# main_board.net
KiCad netlist of a schematic drawn in EAGLE
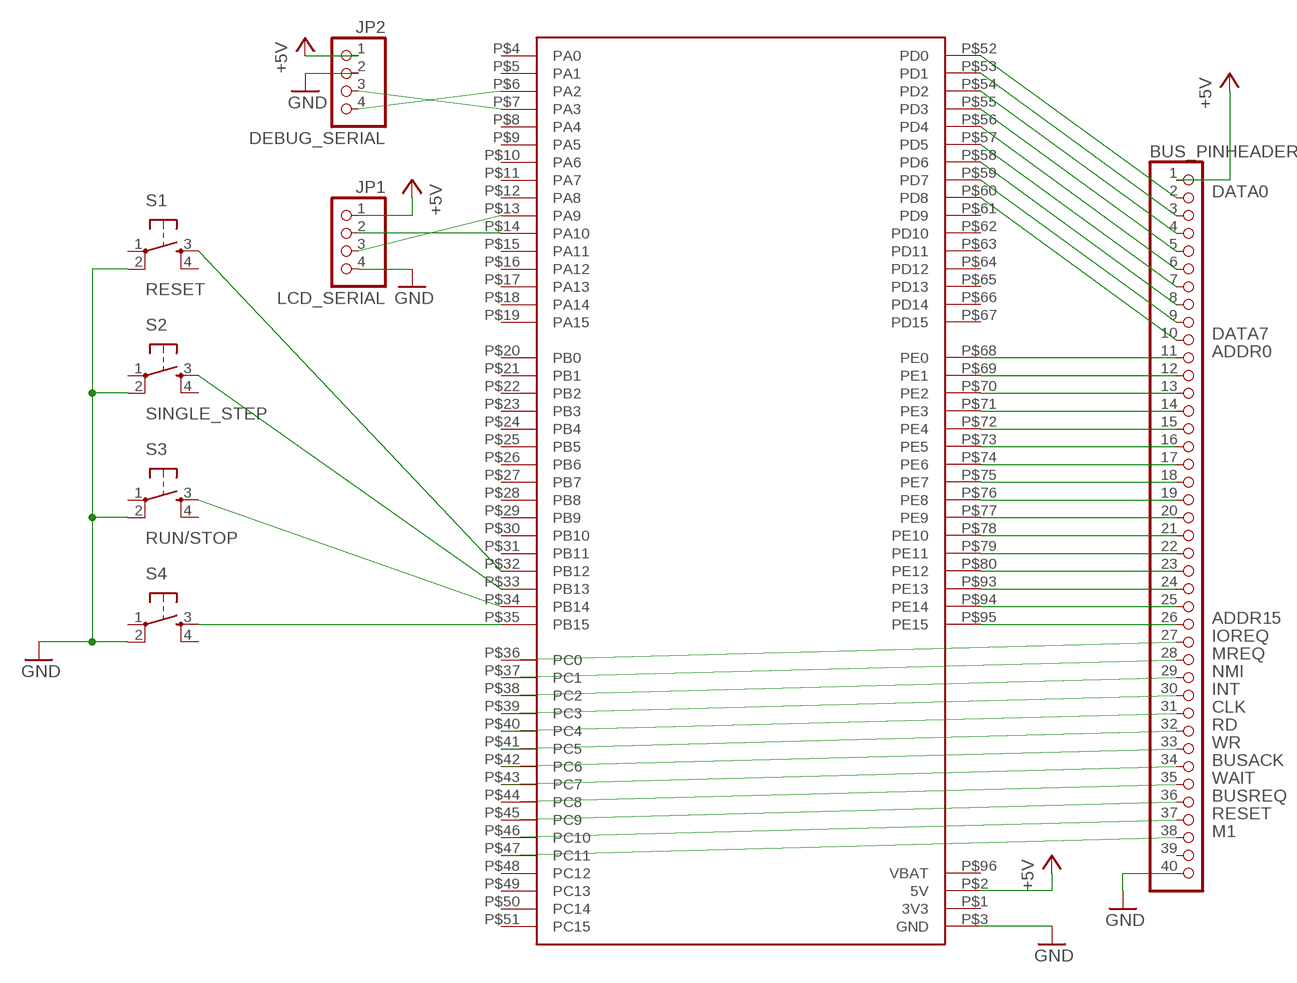
[diagram p0: schematic, sheet 1]

(export (version "E")
  (design (tool "Eeschema 10.0.6"))
  (components
    (comp (ref "BUS_PINHEADER")
      (value "PINHD-1X40")
      (footprint "eagle-import:1X40")
      (libsource (lib "eagle-import") (part "PINHD-1X40"))
    )
    (comp (ref "JP1")
      (value "LCD_SERIAL")
      (footprint "eagle-import:1X04")
      (libsource (lib "eagle-import") (part "PINHD-1X4"))
    )
    (comp (ref "JP2")
      (value "DEBUG_SERIAL")
      (footprint "eagle-import:1X04")
      (libsource (lib "eagle-import") (part "PINHD-1X4"))
    )
    (comp (ref "S1")
      (value "RESET")
      (footprint "eagle-import:TACTILE-PTH")
      (libsource (lib "eagle-import") (part "TAC_SWITCHPTH"))
    )
    (comp (ref "S2")
      (value "SINGLE_STEP")
      (footprint "eagle-import:TACTILE-PTH")
      (libsource (lib "eagle-import") (part "TAC_SWITCHPTH"))
    )
    (comp (ref "S3")
      (value "RUN/STOP")
      (footprint "eagle-import:TACTILE-PTH")
      (libsource (lib "eagle-import") (part "TAC_SWITCHPTH"))
    )
    (comp (ref "S4")
      (value "TAC_SWITCHPTH")
      (footprint "eagle-import:TACTILE-PTH")
      (libsource (lib "eagle-import") (part "TAC_SWITCHPTH"))
    )
    (comp (ref "U$1")
      (value "STM32F103VCT6_BOARD_DEVICE")
      (footprint "eagle-import:STM32F103VCT6_PACK")
      (libsource (lib "eagle-import") (part "STM32F103VCT6_BOARD_DEVICE"))
    )
  )
  (nets
    (net (code "1") (name "+5V") (class "Default")
      (node (ref "BUS_PINHEADER") (pin "1") (pinfunction "1_1") (pintype "passive"))
      (node (ref "JP1") (pin "1") (pinfunction "1_1") (pintype "passive"))
      (node (ref "JP2") (pin "1") (pinfunction "1_1") (pintype "passive"))
      (node (ref "U$1") (pin "P$2") (pinfunction "5V_P$2") (pintype "bidirectional"))
    )
    (net (code "2") (name "/ADDR0") (class "Default")
      (node (ref "BUS_PINHEADER") (pin "11") (pinfunction "11_11") (pintype "passive"))
      (node (ref "U$1") (pin "P$68") (pinfunction "PE0_P$68") (pintype "bidirectional"))
    )
    (net (code "3") (name "/ADDR15") (class "Default")
      (node (ref "BUS_PINHEADER") (pin "26") (pinfunction "26_26") (pintype "passive"))
      (node (ref "U$1") (pin "P$95") (pinfunction "PE15_P$95") (pintype "bidirectional"))
    )
    (net (code "4") (name "/BUSACK") (class "Default")
      (node (ref "BUS_PINHEADER") (pin "34") (pinfunction "34_34") (pintype "passive"))
      (node (ref "U$1") (pin "P$43") (pinfunction "PC7_P$43") (pintype "bidirectional"))
    )
    (net (code "5") (name "/BUSREQ") (class "Default")
      (node (ref "BUS_PINHEADER") (pin "36") (pinfunction "36_36") (pintype "passive"))
      (node (ref "U$1") (pin "P$45") (pinfunction "PC9_P$45") (pintype "bidirectional"))
    )
    (net (code "6") (name "/CLK") (class "Default")
      (node (ref "BUS_PINHEADER") (pin "31") (pinfunction "31_31") (pintype "passive"))
      (node (ref "U$1") (pin "P$40") (pinfunction "PC4_P$40") (pintype "bidirectional"))
    )
    (net (code "7") (name "/DATA0") (class "Default")
      (node (ref "BUS_PINHEADER") (pin "2") (pinfunction "2_2") (pintype "passive"))
      (node (ref "U$1") (pin "P$52") (pinfunction "PD0_P$52") (pintype "bidirectional"))
    )
    (net (code "8") (name "/DATA7") (class "Default")
      (node (ref "BUS_PINHEADER") (pin "10") (pinfunction "10_10") (pintype "passive"))
      (node (ref "U$1") (pin "P$60") (pinfunction "PD8_P$60") (pintype "bidirectional"))
    )
    (net (code "9") (name "/INT") (class "Default")
      (node (ref "BUS_PINHEADER") (pin "30") (pinfunction "30_30") (pintype "passive"))
      (node (ref "U$1") (pin "P$39") (pinfunction "PC3_P$39") (pintype "bidirectional"))
    )
    (net (code "10") (name "/IOREQ") (class "Default")
      (node (ref "BUS_PINHEADER") (pin "27") (pinfunction "27_27") (pintype "passive"))
      (node (ref "U$1") (pin "P$36") (pinfunction "PC0_P$36") (pintype "bidirectional"))
    )
    (net (code "11") (name "/M1") (class "Default")
      (node (ref "BUS_PINHEADER") (pin "38") (pinfunction "38_38") (pintype "passive"))
      (node (ref "U$1") (pin "P$47") (pinfunction "PC11_P$47") (pintype "bidirectional"))
    )
    (net (code "12") (name "/MREQ") (class "Default")
      (node (ref "BUS_PINHEADER") (pin "28") (pinfunction "28_28") (pintype "passive"))
      (node (ref "U$1") (pin "P$37") (pinfunction "PC1_P$37") (pintype "bidirectional"))
    )
    (net (code "13") (name "/NMI") (class "Default")
      (node (ref "BUS_PINHEADER") (pin "29") (pinfunction "29_29") (pintype "passive"))
      (node (ref "U$1") (pin "P$38") (pinfunction "PC2_P$38") (pintype "bidirectional"))
    )
    (net (code "14") (name "/RD") (class "Default")
      (node (ref "BUS_PINHEADER") (pin "32") (pinfunction "32_32") (pintype "passive"))
      (node (ref "U$1") (pin "P$41") (pinfunction "PC5_P$41") (pintype "bidirectional"))
    )
    (net (code "15") (name "/RESET") (class "Default")
      (node (ref "BUS_PINHEADER") (pin "37") (pinfunction "37_37") (pintype "passive"))
      (node (ref "U$1") (pin "P$46") (pinfunction "PC10_P$46") (pintype "bidirectional"))
    )
    (net (code "16") (name "/WAIT") (class "Default")
      (node (ref "BUS_PINHEADER") (pin "35") (pinfunction "35_35") (pintype "passive"))
      (node (ref "U$1") (pin "P$44") (pinfunction "PC8_P$44") (pintype "bidirectional"))
    )
    (net (code "17") (name "/WR") (class "Default")
      (node (ref "BUS_PINHEADER") (pin "33") (pinfunction "33_33") (pintype "passive"))
      (node (ref "U$1") (pin "P$42") (pinfunction "PC6_P$42") (pintype "bidirectional"))
    )
    (net (code "18") (name "GND") (class "Default")
      (node (ref "BUS_PINHEADER") (pin "40") (pinfunction "40_40") (pintype "passive"))
      (node (ref "JP1") (pin "4") (pinfunction "4_4") (pintype "passive"))
      (node (ref "JP2") (pin "2") (pinfunction "2_2") (pintype "passive"))
      (node (ref "S1") (pin "2") (pinfunction "2_2") (pintype "passive"))
      (node (ref "S2") (pin "2") (pinfunction "2_2") (pintype "passive"))
      (node (ref "S3") (pin "2") (pinfunction "2_2") (pintype "passive"))
      (node (ref "S4") (pin "2") (pinfunction "2_2") (pintype "passive"))
      (node (ref "U$1") (pin "P$3") (pinfunction "GND_P$3") (pintype "bidirectional"))
    )
    (net (code "19") (name "Net-(U$1-PA2)") (class "Default")
      (node (ref "JP2") (pin "4") (pinfunction "4_4") (pintype "passive"))
      (node (ref "U$1") (pin "P$6") (pinfunction "PA2_P$6") (pintype "bidirectional"))
    )
    (net (code "20") (name "Net-(U$1-PA3)") (class "Default")
      (node (ref "JP2") (pin "3") (pinfunction "3_3") (pintype "passive"))
      (node (ref "U$1") (pin "P$7") (pinfunction "PA3_P$7") (pintype "bidirectional"))
    )
    (net (code "21") (name "Net-(U$1-PA9)") (class "Default")
      (node (ref "JP1") (pin "3") (pinfunction "3_3") (pintype "passive"))
      (node (ref "U$1") (pin "P$13") (pinfunction "PA9_P$13") (pintype "bidirectional"))
    )
    (net (code "22") (name "Net-(U$1-PA10)") (class "Default")
      (node (ref "JP1") (pin "2") (pinfunction "2_2") (pintype "passive"))
      (node (ref "U$1") (pin "P$14") (pinfunction "PA10_P$14") (pintype "bidirectional"))
    )
    (net (code "23") (name "Net-(U$1-PB12)") (class "Default")
      (node (ref "S1") (pin "3") (pinfunction "3_3") (pintype "passive"))
      (node (ref "U$1") (pin "P$32") (pinfunction "PB12_P$32") (pintype "bidirectional"))
    )
    (net (code "24") (name "Net-(U$1-PB13)") (class "Default")
      (node (ref "S2") (pin "3") (pinfunction "3_3") (pintype "passive"))
      (node (ref "U$1") (pin "P$33") (pinfunction "PB13_P$33") (pintype "bidirectional"))
    )
    (net (code "25") (name "Net-(U$1-PB14)") (class "Default")
      (node (ref "S3") (pin "3") (pinfunction "3_3") (pintype "passive"))
      (node (ref "U$1") (pin "P$34") (pinfunction "PB14_P$34") (pintype "bidirectional"))
    )
    (net (code "26") (name "Net-(U$1-PB15)") (class "Default")
      (node (ref "S4") (pin "3") (pinfunction "3_3") (pintype "passive"))
      (node (ref "U$1") (pin "P$35") (pinfunction "PB15_P$35") (pintype "bidirectional"))
    )
    (net (code "27") (name "Net-(U$1-PD1)") (class "Default")
      (node (ref "BUS_PINHEADER") (pin "3") (pinfunction "3_3") (pintype "passive"))
      (node (ref "U$1") (pin "P$53") (pinfunction "PD1_P$53") (pintype "bidirectional"))
    )
    (net (code "28") (name "Net-(U$1-PD2)") (class "Default")
      (node (ref "BUS_PINHEADER") (pin "4") (pinfunction "4_4") (pintype "passive"))
      (node (ref "U$1") (pin "P$54") (pinfunction "PD2_P$54") (pintype "bidirectional"))
    )
    (net (code "29") (name "Net-(U$1-PD3)") (class "Default")
      (node (ref "BUS_PINHEADER") (pin "5") (pinfunction "5_5") (pintype "passive"))
      (node (ref "U$1") (pin "P$55") (pinfunction "PD3_P$55") (pintype "bidirectional"))
    )
    (net (code "30") (name "Net-(U$1-PD4)") (class "Default")
      (node (ref "BUS_PINHEADER") (pin "6") (pinfunction "6_6") (pintype "passive"))
      (node (ref "U$1") (pin "P$56") (pinfunction "PD4_P$56") (pintype "bidirectional"))
    )
    (net (code "31") (name "Net-(U$1-PD5)") (class "Default")
      (node (ref "BUS_PINHEADER") (pin "7") (pinfunction "7_7") (pintype "passive"))
      (node (ref "U$1") (pin "P$57") (pinfunction "PD5_P$57") (pintype "bidirectional"))
    )
    (net (code "32") (name "Net-(U$1-PD6)") (class "Default")
      (node (ref "BUS_PINHEADER") (pin "8") (pinfunction "8_8") (pintype "passive"))
      (node (ref "U$1") (pin "P$58") (pinfunction "PD6_P$58") (pintype "bidirectional"))
    )
    (net (code "33") (name "Net-(U$1-PD7)") (class "Default")
      (node (ref "BUS_PINHEADER") (pin "9") (pinfunction "9_9") (pintype "passive"))
      (node (ref "U$1") (pin "P$59") (pinfunction "PD7_P$59") (pintype "bidirectional"))
    )
    (net (code "34") (name "Net-(U$1-PE1)") (class "Default")
      (node (ref "BUS_PINHEADER") (pin "12") (pinfunction "12_12") (pintype "passive"))
      (node (ref "U$1") (pin "P$69") (pinfunction "PE1_P$69") (pintype "bidirectional"))
    )
    (net (code "35") (name "Net-(U$1-PE2)") (class "Default")
      (node (ref "BUS_PINHEADER") (pin "13") (pinfunction "13_13") (pintype "passive"))
      (node (ref "U$1") (pin "P$70") (pinfunction "PE2_P$70") (pintype "bidirectional"))
    )
    (net (code "36") (name "Net-(U$1-PE3)") (class "Default")
      (node (ref "BUS_PINHEADER") (pin "14") (pinfunction "14_14") (pintype "passive"))
      (node (ref "U$1") (pin "P$71") (pinfunction "PE3_P$71") (pintype "bidirectional"))
    )
    (net (code "37") (name "Net-(U$1-PE4)") (class "Default")
      (node (ref "BUS_PINHEADER") (pin "15") (pinfunction "15_15") (pintype "passive"))
      (node (ref "U$1") (pin "P$72") (pinfunction "PE4_P$72") (pintype "bidirectional"))
    )
    (net (code "38") (name "Net-(U$1-PE5)") (class "Default")
      (node (ref "BUS_PINHEADER") (pin "16") (pinfunction "16_16") (pintype "passive"))
      (node (ref "U$1") (pin "P$73") (pinfunction "PE5_P$73") (pintype "bidirectional"))
    )
    (net (code "39") (name "Net-(U$1-PE6)") (class "Default")
      (node (ref "BUS_PINHEADER") (pin "17") (pinfunction "17_17") (pintype "passive"))
      (node (ref "U$1") (pin "P$74") (pinfunction "PE6_P$74") (pintype "bidirectional"))
    )
    (net (code "40") (name "Net-(U$1-PE7)") (class "Default")
      (node (ref "BUS_PINHEADER") (pin "18") (pinfunction "18_18") (pintype "passive"))
      (node (ref "U$1") (pin "P$75") (pinfunction "PE7_P$75") (pintype "bidirectional"))
    )
    (net (code "41") (name "Net-(U$1-PE8)") (class "Default")
      (node (ref "BUS_PINHEADER") (pin "19") (pinfunction "19_19") (pintype "passive"))
      (node (ref "U$1") (pin "P$76") (pinfunction "PE8_P$76") (pintype "bidirectional"))
    )
    (net (code "42") (name "Net-(U$1-PE9)") (class "Default")
      (node (ref "BUS_PINHEADER") (pin "20") (pinfunction "20_20") (pintype "passive"))
      (node (ref "U$1") (pin "P$77") (pinfunction "PE9_P$77") (pintype "bidirectional"))
    )
    (net (code "43") (name "Net-(U$1-PE10)") (class "Default")
      (node (ref "BUS_PINHEADER") (pin "21") (pinfunction "21_21") (pintype "passive"))
      (node (ref "U$1") (pin "P$78") (pinfunction "PE10_P$78") (pintype "bidirectional"))
    )
    (net (code "44") (name "Net-(U$1-PE11)") (class "Default")
      (node (ref "BUS_PINHEADER") (pin "22") (pinfunction "22_22") (pintype "passive"))
      (node (ref "U$1") (pin "P$79") (pinfunction "PE11_P$79") (pintype "bidirectional"))
    )
    (net (code "45") (name "Net-(U$1-PE12)") (class "Default")
      (node (ref "BUS_PINHEADER") (pin "23") (pinfunction "23_23") (pintype "passive"))
      (node (ref "U$1") (pin "P$80") (pinfunction "PE12_P$80") (pintype "bidirectional"))
    )
    (net (code "46") (name "Net-(U$1-PE13)") (class "Default")
      (node (ref "BUS_PINHEADER") (pin "24") (pinfunction "24_24") (pintype "passive"))
      (node (ref "U$1") (pin "P$93") (pinfunction "PE13_P$93") (pintype "bidirectional"))
    )
    (net (code "47") (name "Net-(U$1-PE14)") (class "Default")
      (node (ref "BUS_PINHEADER") (pin "25") (pinfunction "25_25") (pintype "passive"))
      (node (ref "U$1") (pin "P$94") (pinfunction "PE14_P$94") (pintype "bidirectional"))
    )
    (net (code "48") (name "unconnected-(BUS_PINHEADER-Pad39)") (class "Default")
      (node (ref "BUS_PINHEADER") (pin "39") (pinfunction "39_39") (pintype "passive"))
    )
    (net (code "49") (name "unconnected-(S1-Pad1)") (class "Default")
      (node (ref "S1") (pin "1") (pinfunction "1_1") (pintype "passive"))
    )
    (net (code "50") (name "unconnected-(S1-Pad4)") (class "Default")
      (node (ref "S1") (pin "4") (pinfunction "4_4") (pintype "passive"))
    )
    (net (code "51") (name "unconnected-(S2-Pad1)") (class "Default")
      (node (ref "S2") (pin "1") (pinfunction "1_1") (pintype "passive"))
    )
    (net (code "52") (name "unconnected-(S2-Pad4)") (class "Default")
      (node (ref "S2") (pin "4") (pinfunction "4_4") (pintype "passive"))
    )
    (net (code "53") (name "unconnected-(S3-Pad1)") (class "Default")
      (node (ref "S3") (pin "1") (pinfunction "1_1") (pintype "passive"))
    )
    (net (code "54") (name "unconnected-(S3-Pad4)") (class "Default")
      (node (ref "S3") (pin "4") (pinfunction "4_4") (pintype "passive"))
    )
    (net (code "55") (name "unconnected-(S4-Pad1)") (class "Default")
      (node (ref "S4") (pin "1") (pinfunction "1_1") (pintype "passive"))
    )
    (net (code "56") (name "unconnected-(S4-Pad4)") (class "Default")
      (node (ref "S4") (pin "4") (pinfunction "4_4") (pintype "passive"))
    )
    (net (code "57") (name "unconnected-(U$1-3V3-PadP$1)") (class "Default")
      (node (ref "U$1") (pin "P$1") (pinfunction "3V3_P$1") (pintype "bidirectional"))
    )
    (net (code "58") (name "unconnected-(U$1-PA0-PadP$4)") (class "Default")
      (node (ref "U$1") (pin "P$4") (pinfunction "PA0_P$4") (pintype "bidirectional"))
    )
    (net (code "59") (name "unconnected-(U$1-PA1-PadP$5)") (class "Default")
      (node (ref "U$1") (pin "P$5") (pinfunction "PA1_P$5") (pintype "bidirectional"))
    )
    (net (code "60") (name "unconnected-(U$1-PA4-PadP$8)") (class "Default")
      (node (ref "U$1") (pin "P$8") (pinfunction "PA4_P$8") (pintype "bidirectional"))
    )
    (net (code "61") (name "unconnected-(U$1-PA5-PadP$9)") (class "Default")
      (node (ref "U$1") (pin "P$9") (pinfunction "PA5_P$9") (pintype "bidirectional"))
    )
    (net (code "62") (name "unconnected-(U$1-PA6-PadP$10)") (class "Default")
      (node (ref "U$1") (pin "P$10") (pinfunction "PA6_P$10") (pintype "bidirectional"))
    )
    (net (code "63") (name "unconnected-(U$1-PA7-PadP$11)") (class "Default")
      (node (ref "U$1") (pin "P$11") (pinfunction "PA7_P$11") (pintype "bidirectional"))
    )
    (net (code "64") (name "unconnected-(U$1-PA8-PadP$12)") (class "Default")
      (node (ref "U$1") (pin "P$12") (pinfunction "PA8_P$12") (pintype "bidirectional"))
    )
    (net (code "65") (name "unconnected-(U$1-PA11-PadP$15)") (class "Default")
      (node (ref "U$1") (pin "P$15") (pinfunction "PA11_P$15") (pintype "bidirectional"))
    )
    (net (code "66") (name "unconnected-(U$1-PA12-PadP$16)") (class "Default")
      (node (ref "U$1") (pin "P$16") (pinfunction "PA12_P$16") (pintype "bidirectional"))
    )
    (net (code "67") (name "unconnected-(U$1-PA13-PadP$17)") (class "Default")
      (node (ref "U$1") (pin "P$17") (pinfunction "PA13_P$17") (pintype "bidirectional"))
    )
    (net (code "68") (name "unconnected-(U$1-PA14-PadP$18)") (class "Default")
      (node (ref "U$1") (pin "P$18") (pinfunction "PA14_P$18") (pintype "bidirectional"))
    )
    (net (code "69") (name "unconnected-(U$1-PA15-PadP$19)") (class "Default")
      (node (ref "U$1") (pin "P$19") (pinfunction "PA15_P$19") (pintype "bidirectional"))
    )
    (net (code "70") (name "unconnected-(U$1-PB0-PadP$20)") (class "Default")
      (node (ref "U$1") (pin "P$20") (pinfunction "PB0_P$20") (pintype "bidirectional"))
    )
    (net (code "71") (name "unconnected-(U$1-PB1-PadP$21)") (class "Default")
      (node (ref "U$1") (pin "P$21") (pinfunction "PB1_P$21") (pintype "bidirectional"))
    )
    (net (code "72") (name "unconnected-(U$1-PB2-PadP$22)") (class "Default")
      (node (ref "U$1") (pin "P$22") (pinfunction "PB2_P$22") (pintype "bidirectional"))
    )
    (net (code "73") (name "unconnected-(U$1-PB3-PadP$23)") (class "Default")
      (node (ref "U$1") (pin "P$23") (pinfunction "PB3_P$23") (pintype "bidirectional"))
    )
    (net (code "74") (name "unconnected-(U$1-PB4-PadP$24)") (class "Default")
      (node (ref "U$1") (pin "P$24") (pinfunction "PB4_P$24") (pintype "bidirectional"))
    )
    (net (code "75") (name "unconnected-(U$1-PB5-PadP$25)") (class "Default")
      (node (ref "U$1") (pin "P$25") (pinfunction "PB5_P$25") (pintype "bidirectional"))
    )
    (net (code "76") (name "unconnected-(U$1-PB6-PadP$26)") (class "Default")
      (node (ref "U$1") (pin "P$26") (pinfunction "PB6_P$26") (pintype "bidirectional"))
    )
    (net (code "77") (name "unconnected-(U$1-PB7-PadP$27)") (class "Default")
      (node (ref "U$1") (pin "P$27") (pinfunction "PB7_P$27") (pintype "bidirectional"))
    )
    (net (code "78") (name "unconnected-(U$1-PB8-PadP$28)") (class "Default")
      (node (ref "U$1") (pin "P$28") (pinfunction "PB8_P$28") (pintype "bidirectional"))
    )
    (net (code "79") (name "unconnected-(U$1-PB9-PadP$29)") (class "Default")
      (node (ref "U$1") (pin "P$29") (pinfunction "PB9_P$29") (pintype "bidirectional"))
    )
    (net (code "80") (name "unconnected-(U$1-PB10-PadP$30)") (class "Default")
      (node (ref "U$1") (pin "P$30") (pinfunction "PB10_P$30") (pintype "bidirectional"))
    )
    (net (code "81") (name "unconnected-(U$1-PB11-PadP$31)") (class "Default")
      (node (ref "U$1") (pin "P$31") (pinfunction "PB11_P$31") (pintype "bidirectional"))
    )
    (net (code "82") (name "unconnected-(U$1-PC12-PadP$48)") (class "Default")
      (node (ref "U$1") (pin "P$48") (pinfunction "PC12_P$48") (pintype "bidirectional"))
    )
    (net (code "83") (name "unconnected-(U$1-PC13-PadP$49)") (class "Default")
      (node (ref "U$1") (pin "P$49") (pinfunction "PC13_P$49") (pintype "bidirectional"))
    )
    (net (code "84") (name "unconnected-(U$1-PC14-PadP$50)") (class "Default")
      (node (ref "U$1") (pin "P$50") (pinfunction "PC14_P$50") (pintype "bidirectional"))
    )
    (net (code "85") (name "unconnected-(U$1-PC15-PadP$51)") (class "Default")
      (node (ref "U$1") (pin "P$51") (pinfunction "PC15_P$51") (pintype "bidirectional"))
    )
    (net (code "86") (name "unconnected-(U$1-PD9-PadP$61)") (class "Default")
      (node (ref "U$1") (pin "P$61") (pinfunction "PD9_P$61") (pintype "bidirectional"))
    )
    (net (code "87") (name "unconnected-(U$1-PD10-PadP$62)") (class "Default")
      (node (ref "U$1") (pin "P$62") (pinfunction "PD10_P$62") (pintype "bidirectional"))
    )
    (net (code "88") (name "unconnected-(U$1-PD11-PadP$63)") (class "Default")
      (node (ref "U$1") (pin "P$63") (pinfunction "PD11_P$63") (pintype "bidirectional"))
    )
    (net (code "89") (name "unconnected-(U$1-PD12-PadP$64)") (class "Default")
      (node (ref "U$1") (pin "P$64") (pinfunction "PD12_P$64") (pintype "bidirectional"))
    )
    (net (code "90") (name "unconnected-(U$1-PD13-PadP$65)") (class "Default")
      (node (ref "U$1") (pin "P$65") (pinfunction "PD13_P$65") (pintype "bidirectional"))
    )
    (net (code "91") (name "unconnected-(U$1-PD14-PadP$66)") (class "Default")
      (node (ref "U$1") (pin "P$66") (pinfunction "PD14_P$66") (pintype "bidirectional"))
    )
    (net (code "92") (name "unconnected-(U$1-PD15-PadP$67)") (class "Default")
      (node (ref "U$1") (pin "P$67") (pinfunction "PD15_P$67") (pintype "bidirectional"))
    )
    (net (code "93") (name "unconnected-(U$1-VBAT-PadP$96)") (class "Default")
      (node (ref "U$1") (pin "P$96") (pinfunction "VBAT_P$96") (pintype "bidirectional"))
    )
  )
)
